# PCA9685.net
KiCad netlist of a schematic drawn in Altium Designer
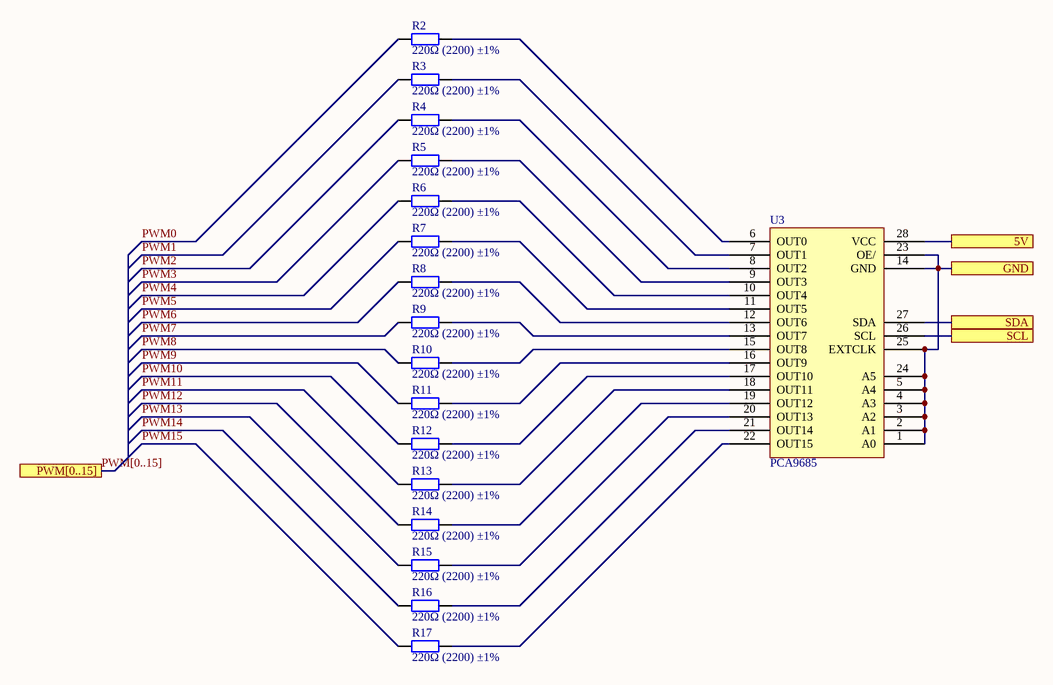
[diagram p0: PCA9685.SchDoc]

(export (version "E")
  (design (tool "Eeschema 10.0.6"))
  (components
    (comp (ref "R2")
      (value "220Ω (2200) ±1%")
      (footprint "0402_R")
      (description "贴片电阻")
      (libsource (lib "Miscellaneous Devices LC") (part "0402 220Ω (2200) 1%"))
    )
    (comp (ref "R3")
      (value "220Ω (2200) ±1%")
      (footprint "0402_R")
      (description "贴片电阻")
      (libsource (lib "Miscellaneous Devices LC") (part "0402 220Ω (2200) 1%"))
    )
    (comp (ref "R4")
      (value "220Ω (2200) ±1%")
      (footprint "0402_R")
      (description "贴片电阻")
      (libsource (lib "Miscellaneous Devices LC") (part "0402 220Ω (2200) 1%"))
    )
    (comp (ref "R5")
      (value "220Ω (2200) ±1%")
      (footprint "0402_R")
      (description "贴片电阻")
      (libsource (lib "Miscellaneous Devices LC") (part "0402 220Ω (2200) 1%"))
    )
    (comp (ref "R6")
      (value "220Ω (2200) ±1%")
      (footprint "0402_R")
      (description "贴片电阻")
      (libsource (lib "Miscellaneous Devices LC") (part "0402 220Ω (2200) 1%"))
    )
    (comp (ref "R7")
      (value "220Ω (2200) ±1%")
      (footprint "0402_R")
      (description "贴片电阻")
      (libsource (lib "Miscellaneous Devices LC") (part "0402 220Ω (2200) 1%"))
    )
    (comp (ref "R8")
      (value "220Ω (2200) ±1%")
      (footprint "0402_R")
      (description "贴片电阻")
      (libsource (lib "Miscellaneous Devices LC") (part "0402 220Ω (2200) 1%"))
    )
    (comp (ref "R9")
      (value "220Ω (2200) ±1%")
      (footprint "0402_R")
      (description "贴片电阻")
      (libsource (lib "Miscellaneous Devices LC") (part "0402 220Ω (2200) 1%"))
    )
    (comp (ref "R10")
      (value "220Ω (2200) ±1%")
      (footprint "0402_R")
      (description "贴片电阻")
      (libsource (lib "Miscellaneous Devices LC") (part "0402 220Ω (2200) 1%"))
    )
    (comp (ref "R11")
      (value "220Ω (2200) ±1%")
      (footprint "0402_R")
      (description "贴片电阻")
      (libsource (lib "Miscellaneous Devices LC") (part "0402 220Ω (2200) 1%"))
    )
    (comp (ref "R12")
      (value "220Ω (2200) ±1%")
      (footprint "0402_R")
      (description "贴片电阻")
      (libsource (lib "Miscellaneous Devices LC") (part "0402 220Ω (2200) 1%"))
    )
    (comp (ref "R13")
      (value "220Ω (2200) ±1%")
      (footprint "0402_R")
      (description "贴片电阻")
      (libsource (lib "Miscellaneous Devices LC") (part "0402 220Ω (2200) 1%"))
    )
    (comp (ref "R14")
      (value "220Ω (2200) ±1%")
      (footprint "0402_R")
      (description "贴片电阻")
      (libsource (lib "Miscellaneous Devices LC") (part "0402 220Ω (2200) 1%"))
    )
    (comp (ref "R15")
      (value "220Ω (2200) ±1%")
      (footprint "0402_R")
      (description "贴片电阻")
      (libsource (lib "Miscellaneous Devices LC") (part "0402 220Ω (2200) 1%"))
    )
    (comp (ref "R16")
      (value "220Ω (2200) ±1%")
      (footprint "0402_R")
      (description "贴片电阻")
      (libsource (lib "Miscellaneous Devices LC") (part "0402 220Ω (2200) 1%"))
    )
    (comp (ref "R17")
      (value "220Ω (2200) ±1%")
      (footprint "0402_R")
      (description "贴片电阻")
      (libsource (lib "Miscellaneous Devices LC") (part "0402 220Ω (2200) 1%"))
    )
    (comp (ref "U3")
      (value "PCA9685")
      (footprint "TSSOP28_M")
      (description "16-channel, 12-bit PWM Fm+ I2C-bus LED controller")
      (libsource (lib "Custom Library") (part "PCA9685"))
    )
  )
  (nets
    (net (code "1") (name "/5V") (class "Default")
      (node (ref "U3") (pin "28") (pinfunction "VCC_28") (pintype "passive"))
    )
    (net (code "2") (name "/GND") (class "Default")
      (node (ref "U3") (pin "1") (pinfunction "A0_1") (pintype "passive"))
      (node (ref "U3") (pin "14") (pinfunction "GND_14") (pintype "passive"))
      (node (ref "U3") (pin "2") (pinfunction "A1_2") (pintype "passive"))
      (node (ref "U3") (pin "23") (pinfunction "OE/_23") (pintype "passive"))
      (node (ref "U3") (pin "24") (pinfunction "A5_24") (pintype "passive"))
      (node (ref "U3") (pin "25") (pinfunction "EXTCLK_25") (pintype "passive"))
      (node (ref "U3") (pin "3") (pinfunction "A2_3") (pintype "passive"))
      (node (ref "U3") (pin "4") (pinfunction "A3_4") (pintype "passive"))
      (node (ref "U3") (pin "5") (pinfunction "A4_5") (pintype "passive"))
    )
    (net (code "3") (name "/PWM0") (class "Default")
      (node (ref "R2") (pin "1") (pinfunction "1_1") (pintype "passive"))
    )
    (net (code "4") (name "/PWM1") (class "Default")
      (node (ref "R3") (pin "1") (pinfunction "1_1") (pintype "passive"))
    )
    (net (code "5") (name "/PWM2") (class "Default")
      (node (ref "R4") (pin "1") (pinfunction "1_1") (pintype "passive"))
    )
    (net (code "6") (name "/PWM3") (class "Default")
      (node (ref "R5") (pin "1") (pinfunction "1_1") (pintype "passive"))
    )
    (net (code "7") (name "/PWM4") (class "Default")
      (node (ref "R6") (pin "1") (pinfunction "1_1") (pintype "passive"))
    )
    (net (code "8") (name "/PWM5") (class "Default")
      (node (ref "R7") (pin "1") (pinfunction "1_1") (pintype "passive"))
    )
    (net (code "9") (name "/PWM6") (class "Default")
      (node (ref "R8") (pin "1") (pinfunction "1_1") (pintype "passive"))
    )
    (net (code "10") (name "/PWM7") (class "Default")
      (node (ref "R9") (pin "1") (pinfunction "1_1") (pintype "passive"))
    )
    (net (code "11") (name "/PWM8") (class "Default")
      (node (ref "R10") (pin "1") (pinfunction "1_1") (pintype "passive"))
    )
    (net (code "12") (name "/PWM9") (class "Default")
      (node (ref "R11") (pin "1") (pinfunction "1_1") (pintype "passive"))
    )
    (net (code "13") (name "/PWM10") (class "Default")
      (node (ref "R12") (pin "1") (pinfunction "1_1") (pintype "passive"))
    )
    (net (code "14") (name "/PWM11") (class "Default")
      (node (ref "R13") (pin "1") (pinfunction "1_1") (pintype "passive"))
    )
    (net (code "15") (name "/PWM12") (class "Default")
      (node (ref "R14") (pin "1") (pinfunction "1_1") (pintype "passive"))
    )
    (net (code "16") (name "/PWM13") (class "Default")
      (node (ref "R15") (pin "1") (pinfunction "1_1") (pintype "passive"))
    )
    (net (code "17") (name "/PWM14") (class "Default")
      (node (ref "R16") (pin "1") (pinfunction "1_1") (pintype "passive"))
    )
    (net (code "18") (name "/PWM15") (class "Default")
      (node (ref "R17") (pin "1") (pinfunction "1_1") (pintype "passive"))
    )
    (net (code "20") (name "/SCL") (class "Default")
      (node (ref "U3") (pin "26") (pinfunction "SCL_26") (pintype "passive"))
    )
    (net (code "21") (name "/SDA") (class "Default")
      (node (ref "U3") (pin "27") (pinfunction "SDA_27") (pintype "passive"))
    )
    (net (code "22") (name "Net-(U3-OUT0)") (class "Default")
      (node (ref "R2") (pin "2") (pinfunction "2_2") (pintype "passive"))
      (node (ref "U3") (pin "6") (pinfunction "OUT0_6") (pintype "passive"))
    )
    (net (code "23") (name "Net-(U3-OUT1)") (class "Default")
      (node (ref "R3") (pin "2") (pinfunction "2_2") (pintype "passive"))
      (node (ref "U3") (pin "7") (pinfunction "OUT1_7") (pintype "passive"))
    )
    (net (code "24") (name "Net-(U3-OUT2)") (class "Default")
      (node (ref "R4") (pin "2") (pinfunction "2_2") (pintype "passive"))
      (node (ref "U3") (pin "8") (pinfunction "OUT2_8") (pintype "passive"))
    )
    (net (code "25") (name "Net-(U3-OUT3)") (class "Default")
      (node (ref "R5") (pin "2") (pinfunction "2_2") (pintype "passive"))
      (node (ref "U3") (pin "9") (pinfunction "OUT3_9") (pintype "passive"))
    )
    (net (code "26") (name "Net-(U3-OUT4)") (class "Default")
      (node (ref "R6") (pin "2") (pinfunction "2_2") (pintype "passive"))
      (node (ref "U3") (pin "10") (pinfunction "OUT4_10") (pintype "passive"))
    )
    (net (code "27") (name "Net-(U3-OUT5)") (class "Default")
      (node (ref "R7") (pin "2") (pinfunction "2_2") (pintype "passive"))
      (node (ref "U3") (pin "11") (pinfunction "OUT5_11") (pintype "passive"))
    )
    (net (code "28") (name "Net-(U3-OUT6)") (class "Default")
      (node (ref "R8") (pin "2") (pinfunction "2_2") (pintype "passive"))
      (node (ref "U3") (pin "12") (pinfunction "OUT6_12") (pintype "passive"))
    )
    (net (code "29") (name "Net-(U3-OUT7)") (class "Default")
      (node (ref "R9") (pin "2") (pinfunction "2_2") (pintype "passive"))
      (node (ref "U3") (pin "13") (pinfunction "OUT7_13") (pintype "passive"))
    )
    (net (code "30") (name "Net-(U3-OUT8)") (class "Default")
      (node (ref "R10") (pin "2") (pinfunction "2_2") (pintype "passive"))
      (node (ref "U3") (pin "15") (pinfunction "OUT8_15") (pintype "passive"))
    )
    (net (code "31") (name "Net-(U3-OUT9)") (class "Default")
      (node (ref "R11") (pin "2") (pinfunction "2_2") (pintype "passive"))
      (node (ref "U3") (pin "16") (pinfunction "OUT9_16") (pintype "passive"))
    )
    (net (code "32") (name "Net-(U3-OUT10)") (class "Default")
      (node (ref "R12") (pin "2") (pinfunction "2_2") (pintype "passive"))
      (node (ref "U3") (pin "17") (pinfunction "OUT10_17") (pintype "passive"))
    )
    (net (code "33") (name "Net-(U3-OUT11)") (class "Default")
      (node (ref "R13") (pin "2") (pinfunction "2_2") (pintype "passive"))
      (node (ref "U3") (pin "18") (pinfunction "OUT11_18") (pintype "passive"))
    )
    (net (code "34") (name "Net-(U3-OUT12)") (class "Default")
      (node (ref "R14") (pin "2") (pinfunction "2_2") (pintype "passive"))
      (node (ref "U3") (pin "19") (pinfunction "OUT12_19") (pintype "passive"))
    )
    (net (code "35") (name "Net-(U3-OUT13)") (class "Default")
      (node (ref "R15") (pin "2") (pinfunction "2_2") (pintype "passive"))
      (node (ref "U3") (pin "20") (pinfunction "OUT13_20") (pintype "passive"))
    )
    (net (code "36") (name "Net-(U3-OUT14)") (class "Default")
      (node (ref "R16") (pin "2") (pinfunction "2_2") (pintype "passive"))
      (node (ref "U3") (pin "21") (pinfunction "OUT14_21") (pintype "passive"))
    )
    (net (code "37") (name "Net-(U3-OUT15)") (class "Default")
      (node (ref "R17") (pin "2") (pinfunction "2_2") (pintype "passive"))
      (node (ref "U3") (pin "22") (pinfunction "OUT15_22") (pintype "passive"))
    )
  )
)
